# sonopi-dac.net
KiCad netlist of a schematic drawn in EAGLE
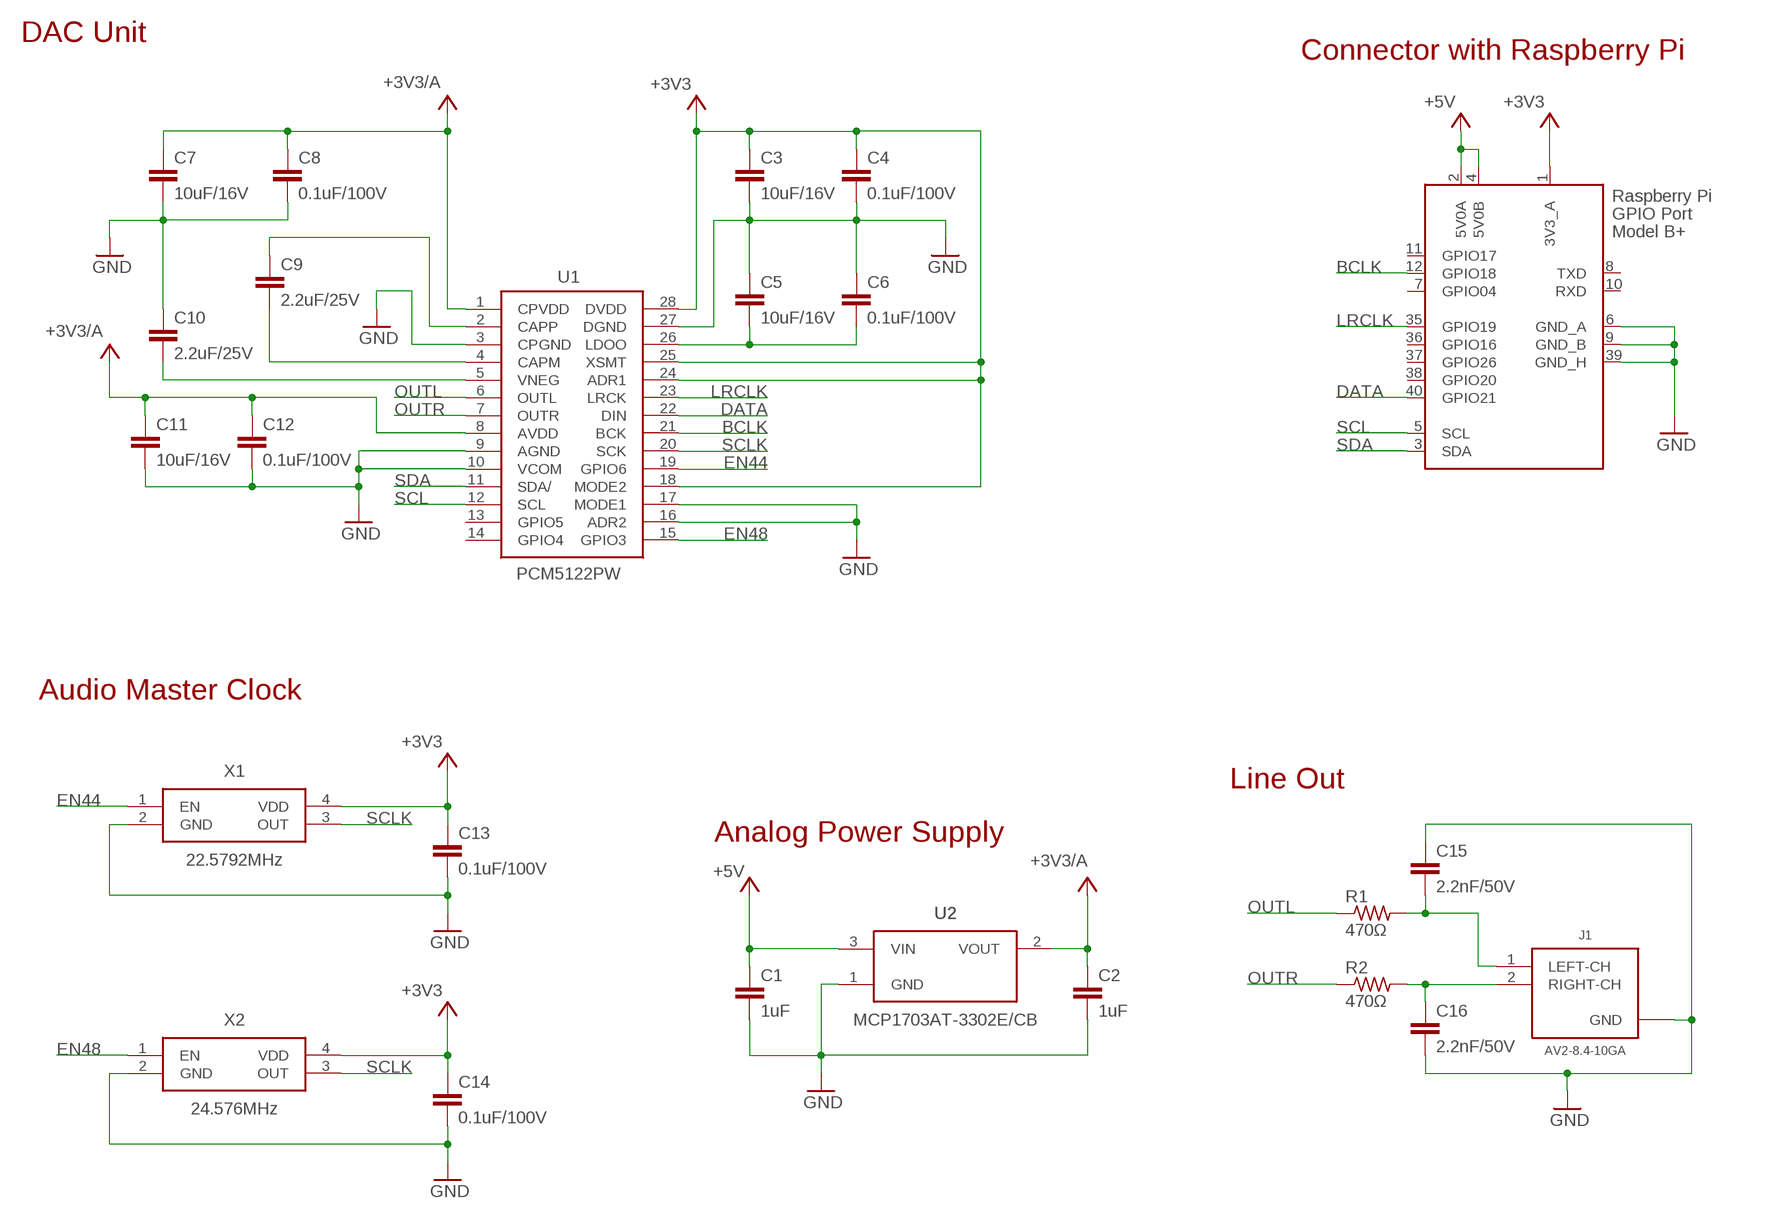
[diagram p0: schematic, sheet 1]

(export (version "E")
  (design (tool "Eeschema 10.0.6"))
  (components
    (comp (ref "C1")
      (value "1uF")
      (footprint "eagle-import:C0603")
      (libsource (lib "eagle-import") (part "C-EUC0603"))
    )
    (comp (ref "C2")
      (value "1uF")
      (footprint "eagle-import:C0603")
      (libsource (lib "eagle-import") (part "C-EUC0603"))
    )
    (comp (ref "C3")
      (value "10uF/16V")
      (footprint "eagle-import:C3216")
      (libsource (lib "eagle-import") (part "C-EUC3216"))
    )
    (comp (ref "C4")
      (value "0.1uF/100V")
      (footprint "eagle-import:C0603")
      (libsource (lib "eagle-import") (part "C-EUC0603"))
    )
    (comp (ref "C5")
      (value "10uF/16V")
      (footprint "eagle-import:C3216")
      (libsource (lib "eagle-import") (part "C-EUC3216"))
    )
    (comp (ref "C6")
      (value "0.1uF/100V")
      (footprint "eagle-import:C0603")
      (libsource (lib "eagle-import") (part "C-EUC0603"))
    )
    (comp (ref "C7")
      (value "10uF/16V")
      (footprint "eagle-import:C3216")
      (libsource (lib "eagle-import") (part "C-EUC3216"))
    )
    (comp (ref "C8")
      (value "0.1uF/100V")
      (footprint "eagle-import:C0603")
      (libsource (lib "eagle-import") (part "C-EUC0603"))
    )
    (comp (ref "C9")
      (value "2.2uF/25V")
      (footprint "eagle-import:C0805")
      (libsource (lib "eagle-import") (part "C-EUC0805"))
    )
    (comp (ref "C10")
      (value "2.2uF/25V")
      (footprint "eagle-import:C0805")
      (libsource (lib "eagle-import") (part "C-EUC0805"))
    )
    (comp (ref "C11")
      (value "10uF/16V")
      (footprint "eagle-import:C3216")
      (libsource (lib "eagle-import") (part "C-EUC3216"))
    )
    (comp (ref "C12")
      (value "0.1uF/100V")
      (footprint "eagle-import:C0603")
      (libsource (lib "eagle-import") (part "C-EUC0603"))
    )
    (comp (ref "C13")
      (value "0.1uF/100V")
      (footprint "eagle-import:C0603")
      (libsource (lib "eagle-import") (part "C-EUC0603"))
    )
    (comp (ref "C14")
      (value "0.1uF/100V")
      (footprint "eagle-import:C0603")
      (libsource (lib "eagle-import") (part "C-EUC0603"))
    )
    (comp (ref "C15")
      (value "2.2nF/50V")
      (footprint "eagle-import:C0603")
      (libsource (lib "eagle-import") (part "C-EUC0603"))
    )
    (comp (ref "C16")
      (value "2.2nF/50V")
      (footprint "eagle-import:C0603")
      (libsource (lib "eagle-import") (part "C-EUC0603"))
    )
    (comp (ref "J1")
      (value "AV2-8.4-10GA")
      (footprint "eagle-import:AV2-8.4-10GA")
      (libsource (lib "eagle-import") (part "2CH-RCAAITENDO"))
    )
    (comp (ref "J2")
      (value "RASPI_BOARD_B+#_ZERO")
      (footprint "eagle-import:RASPI_BOARD_B+HAT_ZERO")
      (libsource (lib "eagle-import") (part "RASPI_BOARD_B+#_ZERO"))
    )
    (comp (ref "R1")
      (value "470Ω")
      (footprint "eagle-import:R0603")
      (libsource (lib "eagle-import") (part "R-US_R0603"))
    )
    (comp (ref "R2")
      (value "470Ω")
      (footprint "eagle-import:R0603")
      (libsource (lib "eagle-import") (part "R-US_R0603"))
    )
    (comp (ref "U1")
      (value "PCM5122PW")
      (footprint "eagle-import:SOP65P640X120-28N")
      (fields (field (name "MOUSER_PART_NUMBER") "595-PCM5122PW") (field (name "RS_PART_NUMBER") "8143732P"))
      (libsource (lib "eagle-import") (part "PCM5122PW"))
    )
    (comp (ref "U2")
      (value "MCP1703AT-3302E/CB")
      (footprint "eagle-import:SOT23")
      (libsource (lib "eagle-import") (part "LDO-REGULATOR"))
    )
    (comp (ref "X1")
      (value "22.5792MHz")
      (footprint "eagle-import:3225-SMD")
      (libsource (lib "eagle-import") (part "OSC-3225"))
    )
    (comp (ref "X2")
      (value "24.576MHz")
      (footprint "eagle-import:3225-SMD")
      (libsource (lib "eagle-import") (part "OSC-3225"))
    )
  )
  (nets
    (net (code "1") (name "+3V3") (class "Default")
      (node (ref "C13") (pin "1") (pinfunction "1_1") (pintype "passive"))
      (node (ref "C14") (pin "1") (pinfunction "1_1") (pintype "passive"))
      (node (ref "C3") (pin "1") (pinfunction "1_1") (pintype "passive"))
      (node (ref "C4") (pin "1") (pinfunction "1_1") (pintype "passive"))
      (node (ref "J2") (pin "1") (pinfunction "3V3_A_1") (pintype "power_in"))
      (node (ref "U1") (pin "18") (pinfunction "MODE2_18") (pintype "bidirectional"))
      (node (ref "U1") (pin "24") (pinfunction "ADR1_24") (pintype "bidirectional"))
      (node (ref "U1") (pin "25") (pinfunction "XSMT_25") (pintype "bidirectional"))
      (node (ref "U1") (pin "28") (pinfunction "DVDD_28") (pintype "bidirectional"))
      (node (ref "X1") (pin "4") (pinfunction "VDD_4") (pintype "power_in"))
      (node (ref "X2") (pin "4") (pinfunction "VDD_4") (pintype "power_in"))
    )
    (net (code "2") (name "+3V3{slash}A") (class "Default")
      (node (ref "C11") (pin "1") (pinfunction "1_1") (pintype "passive"))
      (node (ref "C12") (pin "1") (pinfunction "1_1") (pintype "passive"))
      (node (ref "C2") (pin "1") (pinfunction "1_1") (pintype "passive"))
      (node (ref "C7") (pin "1") (pinfunction "1_1") (pintype "passive"))
      (node (ref "C8") (pin "1") (pinfunction "1_1") (pintype "passive"))
      (node (ref "U1") (pin "1") (pinfunction "CPVDD_1") (pintype "bidirectional"))
      (node (ref "U1") (pin "8") (pinfunction "AVDD_8") (pintype "bidirectional"))
      (node (ref "U2") (pin "2") (pinfunction "VOUT_2") (pintype "bidirectional"))
    )
    (net (code "3") (name "+5V") (class "Default")
      (node (ref "C1") (pin "1") (pinfunction "1_1") (pintype "passive"))
      (node (ref "J2") (pin "2") (pinfunction "5V0A_2") (pintype "power_in"))
      (node (ref "J2") (pin "4") (pinfunction "5V0B_4") (pintype "power_in"))
      (node (ref "U2") (pin "3") (pinfunction "VIN_3") (pintype "bidirectional"))
    )
    (net (code "4") (name "/BCLK") (class "Default")
      (node (ref "J2") (pin "12") (pinfunction "GPIO18_12") (pintype "bidirectional"))
      (node (ref "U1") (pin "21") (pinfunction "BCK_21") (pintype "bidirectional"))
    )
    (net (code "5") (name "/DATA") (class "Default")
      (node (ref "J2") (pin "40") (pinfunction "GPIO21_40") (pintype "bidirectional"))
      (node (ref "U1") (pin "22") (pinfunction "DIN_22") (pintype "bidirectional"))
    )
    (net (code "6") (name "/EN44") (class "Default")
      (node (ref "U1") (pin "19") (pinfunction "GPIO6_19") (pintype "bidirectional"))
      (node (ref "X1") (pin "1") (pinfunction "EN_1") (pintype "bidirectional"))
    )
    (net (code "7") (name "/EN48") (class "Default")
      (node (ref "U1") (pin "15") (pinfunction "GPIO3_15") (pintype "bidirectional"))
      (node (ref "X2") (pin "1") (pinfunction "EN_1") (pintype "bidirectional"))
    )
    (net (code "8") (name "/LRCLK") (class "Default")
      (node (ref "J2") (pin "35") (pinfunction "GPIO19_35") (pintype "bidirectional"))
      (node (ref "U1") (pin "23") (pinfunction "LRCK_23") (pintype "bidirectional"))
    )
    (net (code "9") (name "/OUTL") (class "Default")
      (node (ref "R1") (pin "1") (pinfunction "1_1") (pintype "passive"))
      (node (ref "U1") (pin "6") (pinfunction "OUTL_6") (pintype "bidirectional"))
    )
    (net (code "10") (name "/OUTR") (class "Default")
      (node (ref "R2") (pin "1") (pinfunction "1_1") (pintype "passive"))
      (node (ref "U1") (pin "7") (pinfunction "OUTR_7") (pintype "bidirectional"))
    )
    (net (code "11") (name "/SCL") (class "Default")
      (node (ref "J2") (pin "5") (pinfunction "SCL_5") (pintype "bidirectional"))
      (node (ref "U1") (pin "12") (pinfunction "SCL_12") (pintype "bidirectional"))
    )
    (net (code "12") (name "/SCLK") (class "Default")
      (node (ref "U1") (pin "20") (pinfunction "SCK_20") (pintype "bidirectional"))
      (node (ref "X1") (pin "3") (pinfunction "OUT_3") (pintype "bidirectional"))
      (node (ref "X2") (pin "3") (pinfunction "OUT_3") (pintype "bidirectional"))
    )
    (net (code "13") (name "/SDA") (class "Default")
      (node (ref "J2") (pin "3") (pinfunction "SDA_3") (pintype "bidirectional"))
      (node (ref "U1") (pin "11") (pinfunction "SDA/_11") (pintype "bidirectional"))
    )
    (net (code "14") (name "GND") (class "Default")
      (node (ref "C1") (pin "2") (pinfunction "2_2") (pintype "passive"))
      (node (ref "C10") (pin "1") (pinfunction "1_1") (pintype "passive"))
      (node (ref "C11") (pin "2") (pinfunction "2_2") (pintype "passive"))
      (node (ref "C12") (pin "2") (pinfunction "2_2") (pintype "passive"))
      (node (ref "C13") (pin "2") (pinfunction "2_2") (pintype "passive"))
      (node (ref "C14") (pin "2") (pinfunction "2_2") (pintype "passive"))
      (node (ref "C15") (pin "1") (pinfunction "1_1") (pintype "passive"))
      (node (ref "C16") (pin "2") (pinfunction "2_2") (pintype "passive"))
      (node (ref "C2") (pin "2") (pinfunction "2_2") (pintype "passive"))
      (node (ref "C3") (pin "2") (pinfunction "2_2") (pintype "passive"))
      (node (ref "C4") (pin "2") (pinfunction "2_2") (pintype "passive"))
      (node (ref "C5") (pin "1") (pinfunction "1_1") (pintype "passive"))
      (node (ref "C6") (pin "1") (pinfunction "1_1") (pintype "passive"))
      (node (ref "C7") (pin "2") (pinfunction "2_2") (pintype "passive"))
      (node (ref "C8") (pin "2") (pinfunction "2_2") (pintype "passive"))
      (node (ref "J1") (pin "G1") (pinfunction "GND_G1") (pintype "power_in"))
      (node (ref "J1") (pin "G2") (pinfunction "GND_G2") (pintype "power_in"))
      (node (ref "J1") (pin "G3") (pinfunction "GND_G3") (pintype "power_in"))
      (node (ref "J1") (pin "G4") (pinfunction "GND_G4") (pintype "power_in"))
      (node (ref "J2") (pin "39") (pinfunction "GND_H_39") (pintype "power_in"))
      (node (ref "J2") (pin "6") (pinfunction "GND_A_6") (pintype "power_in"))
      (node (ref "J2") (pin "9") (pinfunction "GND_B_9") (pintype "power_in"))
      (node (ref "U1") (pin "10") (pinfunction "VCOM_10") (pintype "bidirectional"))
      (node (ref "U1") (pin "16") (pinfunction "ADR2_16") (pintype "bidirectional"))
      (node (ref "U1") (pin "17") (pinfunction "MODE1_17") (pintype "bidirectional"))
      (node (ref "U1") (pin "27") (pinfunction "DGND_27") (pintype "bidirectional"))
      (node (ref "U1") (pin "3") (pinfunction "CPGND_3") (pintype "bidirectional"))
      (node (ref "U1") (pin "9") (pinfunction "AGND_9") (pintype "bidirectional"))
      (node (ref "U2") (pin "1") (pinfunction "GND_1") (pintype "bidirectional"))
      (node (ref "X1") (pin "2") (pinfunction "GND_2") (pintype "power_in"))
      (node (ref "X2") (pin "2") (pinfunction "GND_2") (pintype "power_in"))
    )
    (net (code "15") (name "Net-(J1-LEFT-CH)") (class "Default")
      (node (ref "C15") (pin "2") (pinfunction "2_2") (pintype "passive"))
      (node (ref "J1") (pin "1") (pinfunction "LEFT-CH_1") (pintype "bidirectional"))
      (node (ref "R1") (pin "2") (pinfunction "2_2") (pintype "passive"))
    )
    (net (code "16") (name "Net-(J1-RIGHT-CH)") (class "Default")
      (node (ref "C16") (pin "1") (pinfunction "1_1") (pintype "passive"))
      (node (ref "J1") (pin "2") (pinfunction "RIGHT-CH_2") (pintype "bidirectional"))
      (node (ref "R2") (pin "2") (pinfunction "2_2") (pintype "passive"))
    )
    (net (code "17") (name "Net-(U1-CAPM)") (class "Default")
      (node (ref "C9") (pin "2") (pinfunction "2_2") (pintype "passive"))
      (node (ref "U1") (pin "4") (pinfunction "CAPM_4") (pintype "bidirectional"))
    )
    (net (code "18") (name "Net-(U1-CAPP)") (class "Default")
      (node (ref "C9") (pin "1") (pinfunction "1_1") (pintype "passive"))
      (node (ref "U1") (pin "2") (pinfunction "CAPP_2") (pintype "bidirectional"))
    )
    (net (code "19") (name "Net-(U1-LDOO)") (class "Default")
      (node (ref "C5") (pin "2") (pinfunction "2_2") (pintype "passive"))
      (node (ref "C6") (pin "2") (pinfunction "2_2") (pintype "passive"))
      (node (ref "U1") (pin "26") (pinfunction "LDOO_26") (pintype "bidirectional"))
    )
    (net (code "20") (name "Net-(U1-VNEG)") (class "Default")
      (node (ref "C10") (pin "2") (pinfunction "2_2") (pintype "passive"))
      (node (ref "U1") (pin "5") (pinfunction "VNEG_5") (pintype "bidirectional"))
    )
    (net (code "21") (name "unconnected-(J2-GPIO04-Pad7)") (class "Default")
      (node (ref "J2") (pin "7") (pinfunction "GPIO04_7") (pintype "bidirectional"))
    )
    (net (code "22") (name "unconnected-(J2-GPIO16-Pad36)") (class "Default")
      (node (ref "J2") (pin "36") (pinfunction "GPIO16_36") (pintype "bidirectional"))
    )
    (net (code "23") (name "unconnected-(J2-GPIO17-Pad11)") (class "Default")
      (node (ref "J2") (pin "11") (pinfunction "GPIO17_11") (pintype "bidirectional"))
    )
    (net (code "24") (name "unconnected-(J2-GPIO20-Pad38)") (class "Default")
      (node (ref "J2") (pin "38") (pinfunction "GPIO20_38") (pintype "bidirectional"))
    )
    (net (code "25") (name "unconnected-(J2-GPIO26-Pad37)") (class "Default")
      (node (ref "J2") (pin "37") (pinfunction "GPIO26_37") (pintype "bidirectional"))
    )
    (net (code "26") (name "unconnected-(J2-RXD-Pad10)") (class "Default")
      (node (ref "J2") (pin "10") (pinfunction "RXD_10") (pintype "bidirectional"))
    )
    (net (code "27") (name "unconnected-(J2-TXD-Pad8)") (class "Default")
      (node (ref "J2") (pin "8") (pinfunction "TXD_8") (pintype "bidirectional"))
    )
    (net (code "28") (name "unconnected-(U1-GPIO4-Pad14)") (class "Default")
      (node (ref "U1") (pin "14") (pinfunction "GPIO4_14") (pintype "bidirectional"))
    )
    (net (code "29") (name "unconnected-(U1-GPIO5-Pad13)") (class "Default")
      (node (ref "U1") (pin "13") (pinfunction "GPIO5_13") (pintype "bidirectional"))
    )
  )
)
